# uarthid.net
KiCad netlist of a schematic drawn in EAGLE
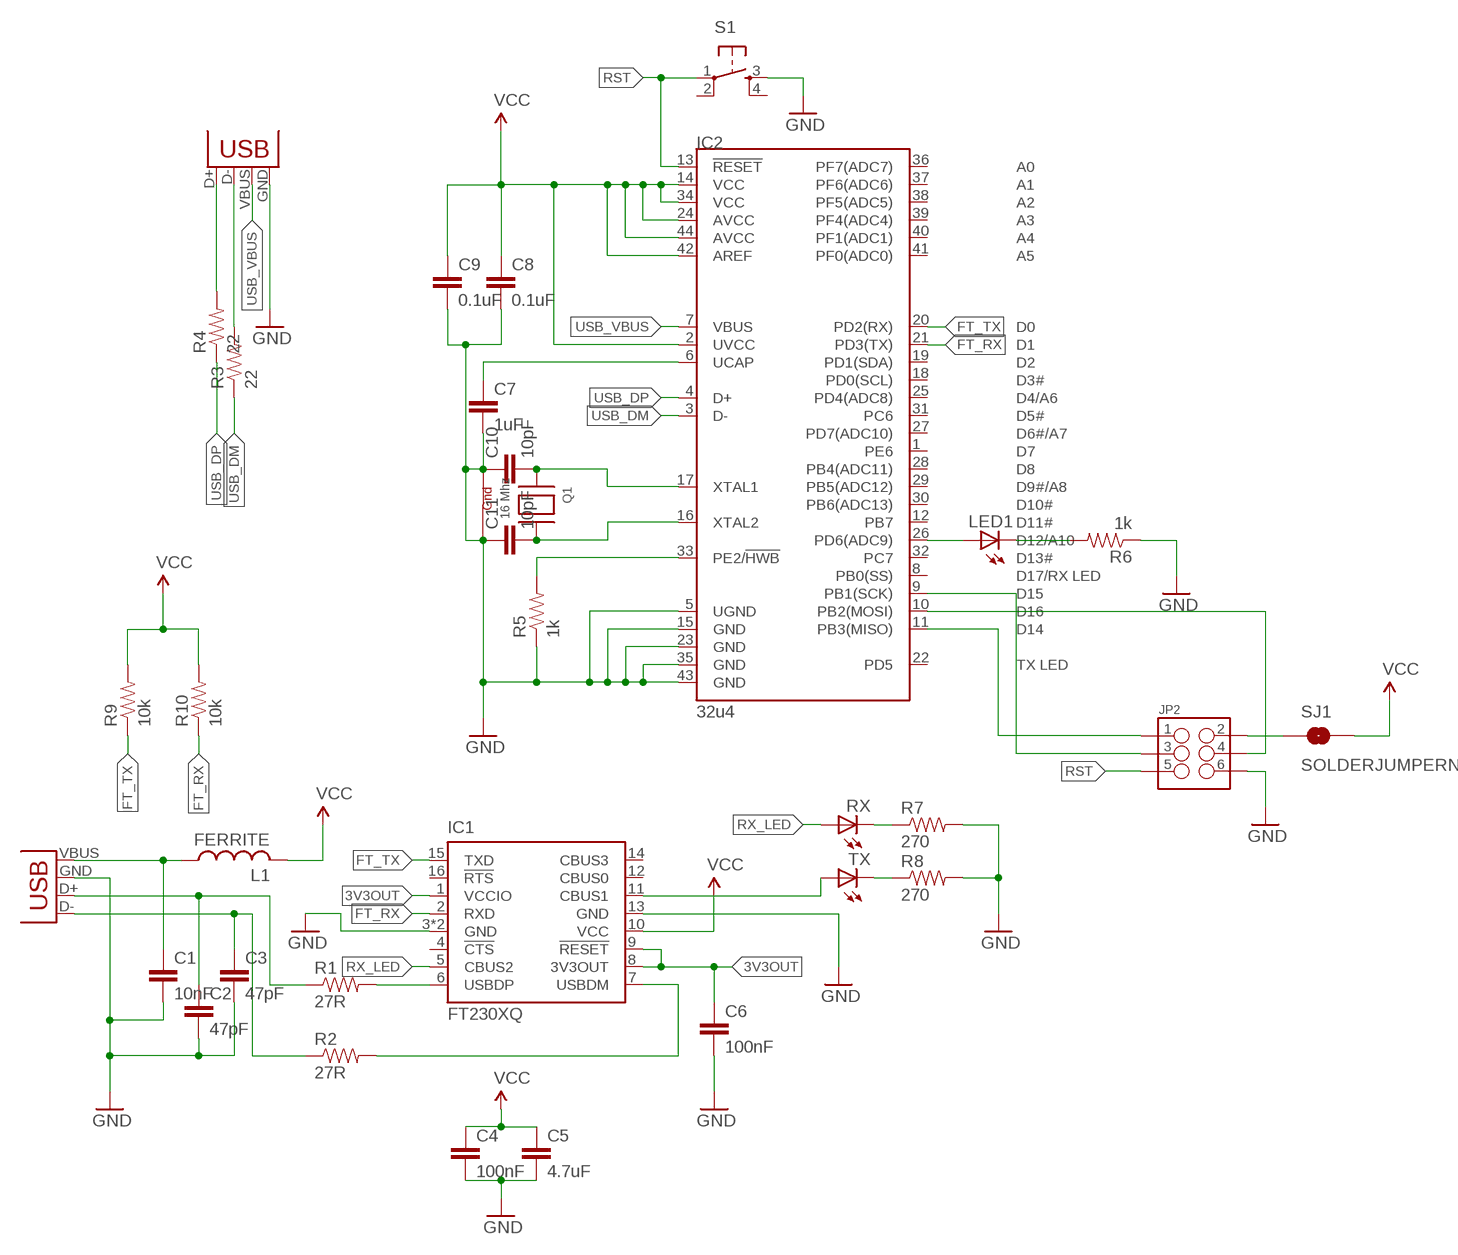
[diagram p0: schematic, sheet 1]

(export (version "E")
  (design (tool "Eeschema 10.0.6"))
  (components
    (comp (ref "C1")
      (value "10nF")
      (footprint "eagle-import:0805")
      (libsource (lib "eagle-import") (part "CAP0805"))
    )
    (comp (ref "C2")
      (value "47pF")
      (footprint "eagle-import:0805")
      (libsource (lib "eagle-import") (part "CAP0805"))
    )
    (comp (ref "C3")
      (value "47pF")
      (footprint "eagle-import:0805")
      (libsource (lib "eagle-import") (part "CAP0805"))
    )
    (comp (ref "C4")
      (value "100nF")
      (footprint "eagle-import:0805")
      (libsource (lib "eagle-import") (part "CAP0805"))
    )
    (comp (ref "C5")
      (value "4.7uF")
      (footprint "eagle-import:0805")
      (libsource (lib "eagle-import") (part "CAP0805"))
    )
    (comp (ref "C6")
      (value "100nF")
      (footprint "eagle-import:0805")
      (libsource (lib "eagle-import") (part "CAP0805"))
    )
    (comp (ref "C7")
      (value "1uF")
      (footprint "eagle-import:0805")
      (libsource (lib "eagle-import") (part "CAP0805"))
    )
    (comp (ref "C8")
      (value "0.1uF")
      (footprint "eagle-import:0805")
      (libsource (lib "eagle-import") (part "CAP0805"))
    )
    (comp (ref "C9")
      (value "0.1uF")
      (footprint "eagle-import:0805")
      (libsource (lib "eagle-import") (part "CAP0805"))
    )
    (comp (ref "C10")
      (value "10pF")
      (footprint "eagle-import:0805")
      (libsource (lib "eagle-import") (part "CAP0805"))
    )
    (comp (ref "C11")
      (value "10pF")
      (footprint "eagle-import:0805")
      (libsource (lib "eagle-import") (part "CAP0805"))
    )
    (comp (ref "IC1")
      (value "FT230XQ")
      (footprint "eagle-import:QFN16")
      (fields (field (name "PARTNO") "FT230XQ-T"))
      (libsource (lib "eagle-import") (part "FT230XQ"))
    )
    (comp (ref "IC2")
      (value "32u4")
      (footprint "eagle-import:SPARKFUN-DIGITALIC_QFN-44")
      (fields (field (name "PARTNO") "ATMEGA32U4RC-MU"))
      (libsource (lib "eagle-import") (part "ATMEGA32U4QFN"))
    )
    (comp (ref "JP1")
      (value "USB-A-H")
      (footprint "eagle-import:USB-A-H")
      (fields (field (name "PARTNO") "1002-015-01001"))
      (libsource (lib "eagle-import") (part "USB-A-H"))
    )
    (comp (ref "JP2")
      (value "M03X22X3_SILK_SM")
      (footprint "eagle-import:2X3")
      (libsource (lib "eagle-import") (part "M03X22X3_SILK_SM"))
    )
    (comp (ref "JP3")
      (value "USBSMD")
      (footprint "eagle-import:USB-MINIB")
      (fields (field (name "PARTNO") "690-005-299-043"))
      (libsource (lib "eagle-import") (part "USBSMD"))
    )
    (comp (ref "L1")
      (value "FERRITE")
      (footprint "eagle-import:0805")
      (fields (field (name "PARTNO") "CIM21J601NE"))
      (libsource (lib "eagle-import") (part "FERRITE"))
    )
    (comp (ref "LED1")
      (value "LEDCHIPLED_0805")
      (footprint "eagle-import:CHIPLED_0805")
      (libsource (lib "eagle-import") (part "LEDCHIPLED_0805"))
    )
    (comp (ref "Q1")
      (value "16 Mhz")
      (footprint "eagle-import:NX3225")
      (fields (field (name "PARTNO") "TSX-3225 16.0000MF18X-AC3"))
      (libsource (lib "eagle-import") (part "XTAL-4-3225"))
    )
    (comp (ref "R1")
      (value "27R")
      (footprint "eagle-import:0805")
      (libsource (lib "eagle-import") (part "RESISTOR0805-RES"))
    )
    (comp (ref "R2")
      (value "27R")
      (footprint "eagle-import:0805")
      (libsource (lib "eagle-import") (part "RESISTOR0805-RES"))
    )
    (comp (ref "R3")
      (value "22")
      (footprint "eagle-import:0805")
      (libsource (lib "eagle-import") (part "RESISTOR0805-RES"))
    )
    (comp (ref "R4")
      (value "22")
      (footprint "eagle-import:0805")
      (libsource (lib "eagle-import") (part "RESISTOR0805-RES"))
    )
    (comp (ref "R5")
      (value "1k")
      (footprint "eagle-import:0805")
      (libsource (lib "eagle-import") (part "RESISTOR0805-RES"))
    )
    (comp (ref "R6")
      (value "1k")
      (footprint "eagle-import:0805")
      (libsource (lib "eagle-import") (part "RESISTOR0805-RES"))
    )
    (comp (ref "R7")
      (value "270")
      (footprint "eagle-import:0805")
      (libsource (lib "eagle-import") (part "RESISTOR0805-RES"))
    )
    (comp (ref "R8")
      (value "270")
      (footprint "eagle-import:0805")
      (libsource (lib "eagle-import") (part "RESISTOR0805-RES"))
    )
    (comp (ref "R9")
      (value "10k")
      (footprint "eagle-import:0805")
      (libsource (lib "eagle-import") (part "RESISTOR0805-RES"))
    )
    (comp (ref "R10")
      (value "10k")
      (footprint "eagle-import:0805")
      (libsource (lib "eagle-import") (part "RESISTOR0805-RES"))
    )
    (comp (ref "RX")
      (value "LEDCHIPLED_0805")
      (footprint "eagle-import:CHIPLED_0805")
      (libsource (lib "eagle-import") (part "LEDCHIPLED_0805"))
    )
    (comp (ref "S1")
      (value "TAC_SWITCHSMD")
      (footprint "eagle-import:TACTILE_SWITCH_SMD")
      (libsource (lib "eagle-import") (part "TAC_SWITCHSMD"))
    )
    (comp (ref "SJ1")
      (value "SOLDERJUMPERNO")
      (footprint "eagle-import:SJ_2S-NO")
      (libsource (lib "eagle-import") (part "SOLDERJUMPERNO"))
    )
    (comp (ref "TX")
      (value "LEDCHIPLED_0805")
      (footprint "eagle-import:CHIPLED_0805")
      (libsource (lib "eagle-import") (part "LEDCHIPLED_0805"))
    )
  )
  (nets
    (net (code "1") (name "3V3OUT") (class "Default")
      (node (ref "C6") (pin "1") (pinfunction "1_1") (pintype "passive"))
      (node (ref "IC1") (pin "1") (pinfunction "VCCIO_1") (pintype "power_in"))
      (node (ref "IC1") (pin "8") (pinfunction "3V3OUT_8") (pintype "output"))
      (node (ref "IC1") (pin "9") (pinfunction "~{RESET}_9") (pintype "input"))
    )
    (net (code "2") (name "FT_RX") (class "Default")
      (node (ref "IC1") (pin "2") (pinfunction "RXD_2") (pintype "input"))
      (node (ref "IC2") (pin "21") (pinfunction "PD3(TX)_21") (pintype "bidirectional"))
      (node (ref "R10") (pin "1") (pinfunction "1_1") (pintype "passive"))
    )
    (net (code "3") (name "FT_TX") (class "Default")
      (node (ref "IC1") (pin "15") (pinfunction "TXD_15") (pintype "output"))
      (node (ref "IC2") (pin "20") (pinfunction "PD2(RX)_20") (pintype "bidirectional"))
      (node (ref "R9") (pin "1") (pinfunction "1_1") (pintype "passive"))
    )
    (net (code "4") (name "GND") (class "Default")
      (node (ref "C1") (pin "2") (pinfunction "2_2") (pintype "passive"))
      (node (ref "C10") (pin "1") (pinfunction "1_1") (pintype "passive"))
      (node (ref "C11") (pin "1") (pinfunction "1_1") (pintype "passive"))
      (node (ref "C2") (pin "2") (pinfunction "2_2") (pintype "passive"))
      (node (ref "C3") (pin "2") (pinfunction "2_2") (pintype "passive"))
      (node (ref "C4") (pin "2") (pinfunction "2_2") (pintype "passive"))
      (node (ref "C5") (pin "2") (pinfunction "2_2") (pintype "passive"))
      (node (ref "C6") (pin "2") (pinfunction "2_2") (pintype "passive"))
      (node (ref "C7") (pin "2") (pinfunction "2_2") (pintype "passive"))
      (node (ref "C8") (pin "2") (pinfunction "2_2") (pintype "passive"))
      (node (ref "C9") (pin "2") (pinfunction "2_2") (pintype "passive"))
      (node (ref "IC1") (pin "13") (pinfunction "GND_13") (pintype "power_in"))
      (node (ref "IC1") (pin "3") (pinfunction "GND_3") (pintype "power_in"))
      (node (ref "IC1") (pin "TAB") (pinfunction "GND_TAB") (pintype "power_in"))
      (node (ref "IC2") (pin "15") (pinfunction "GND_15") (pintype "bidirectional"))
      (node (ref "IC2") (pin "23") (pinfunction "GND_23") (pintype "bidirectional"))
      (node (ref "IC2") (pin "35") (pinfunction "GND_35") (pintype "bidirectional"))
      (node (ref "IC2") (pin "43") (pinfunction "GND_43") (pintype "bidirectional"))
      (node (ref "IC2") (pin "5") (pinfunction "UGND_5") (pintype "bidirectional"))
      (node (ref "JP1") (pin "GND") (pinfunction "VBUS_GND") (pintype "bidirectional"))
      (node (ref "JP2") (pin "6") (pinfunction "6_6") (pintype "bidirectional"))
      (node (ref "JP3") (pin "GND") (pinfunction "GND_GND") (pintype "bidirectional"))
      (node (ref "Q1") (pin "2") (pinfunction "G2_2") (pintype "power_in"))
      (node (ref "Q1") (pin "4") (pinfunction "G1_4") (pintype "power_in"))
      (node (ref "R5") (pin "1") (pinfunction "1_1") (pintype "passive"))
      (node (ref "R6") (pin "1") (pinfunction "1_1") (pintype "passive"))
      (node (ref "R7") (pin "2") (pinfunction "2_2") (pintype "passive"))
      (node (ref "R8") (pin "2") (pinfunction "2_2") (pintype "passive"))
      (node (ref "S1") (pin "3") (pinfunction "3_3") (pintype "passive"))
    )
    (net (code "5") (name "Net-(IC1-CBUS1)") (class "Default")
      (node (ref "IC1") (pin "11") (pinfunction "CBUS1_11") (pintype "bidirectional"))
      (node (ref "TX") (pin "A") (pinfunction "A_A") (pintype "passive"))
    )
    (net (code "6") (name "Net-(IC1-USBDM)") (class "Default")
      (node (ref "IC1") (pin "7") (pinfunction "USBDM_7") (pintype "input"))
      (node (ref "R2") (pin "2") (pinfunction "2_2") (pintype "passive"))
    )
    (net (code "7") (name "Net-(IC1-USBDP)") (class "Default")
      (node (ref "IC1") (pin "6") (pinfunction "USBDP_6") (pintype "input"))
      (node (ref "R1") (pin "2") (pinfunction "2_2") (pintype "passive"))
    )
    (net (code "8") (name "Net-(IC2-PB1(SCK))") (class "Default")
      (node (ref "IC2") (pin "9") (pinfunction "PB1(SCK)_9") (pintype "bidirectional"))
      (node (ref "JP2") (pin "3") (pinfunction "3_3") (pintype "bidirectional"))
    )
    (net (code "9") (name "Net-(IC2-PB2(MOSI))") (class "Default")
      (node (ref "IC2") (pin "10") (pinfunction "PB2(MOSI)_10") (pintype "bidirectional"))
      (node (ref "JP2") (pin "4") (pinfunction "4_4") (pintype "bidirectional"))
    )
    (net (code "10") (name "Net-(IC2-PB3(MISO))") (class "Default")
      (node (ref "IC2") (pin "11") (pinfunction "PB3(MISO)_11") (pintype "bidirectional"))
      (node (ref "JP2") (pin "1") (pinfunction "1_1") (pintype "bidirectional"))
    )
    (net (code "11") (name "Net-(IC2-PD6(ADC9))") (class "Default")
      (node (ref "IC2") (pin "26") (pinfunction "PD6(ADC9)_26") (pintype "bidirectional"))
      (node (ref "LED1") (pin "A") (pinfunction "A_A") (pintype "passive"))
    )
    (net (code "12") (name "Net-(IC2-PE2{slash}~{HWB})") (class "Default")
      (node (ref "IC2") (pin "33") (pinfunction "PE2/~{HWB}_33") (pintype "bidirectional"))
      (node (ref "R5") (pin "2") (pinfunction "2_2") (pintype "passive"))
    )
    (net (code "13") (name "Net-(IC2-UCAP)") (class "Default")
      (node (ref "C7") (pin "1") (pinfunction "1_1") (pintype "passive"))
      (node (ref "IC2") (pin "6") (pinfunction "UCAP_6") (pintype "bidirectional"))
    )
    (net (code "14") (name "Net-(IC2-XTAL1)") (class "Default")
      (node (ref "C10") (pin "2") (pinfunction "2_2") (pintype "passive"))
      (node (ref "IC2") (pin "17") (pinfunction "XTAL1_17") (pintype "bidirectional"))
      (node (ref "Q1") (pin "1") (pinfunction "X1_1") (pintype "bidirectional"))
    )
    (net (code "15") (name "Net-(IC2-XTAL2)") (class "Default")
      (node (ref "C11") (pin "2") (pinfunction "2_2") (pintype "passive"))
      (node (ref "IC2") (pin "16") (pinfunction "XTAL2_16") (pintype "bidirectional"))
      (node (ref "Q1") (pin "3") (pinfunction "X2_3") (pintype "bidirectional"))
    )
    (net (code "16") (name "Net-(JP1-D+)") (class "Default")
      (node (ref "C3") (pin "1") (pinfunction "1_1") (pintype "passive"))
      (node (ref "JP1") (pin "D-") (pinfunction "D+_D-") (pintype "bidirectional"))
      (node (ref "R2") (pin "1") (pinfunction "1_1") (pintype "passive"))
    )
    (net (code "17") (name "Net-(JP1-D-)") (class "Default")
      (node (ref "C2") (pin "1") (pinfunction "1_1") (pintype "passive"))
      (node (ref "JP1") (pin "D+") (pinfunction "D-_D+") (pintype "bidirectional"))
      (node (ref "R1") (pin "1") (pinfunction "1_1") (pintype "passive"))
    )
    (net (code "18") (name "Net-(JP1-GND)") (class "Default")
      (node (ref "C1") (pin "1") (pinfunction "1_1") (pintype "passive"))
      (node (ref "JP1") (pin "VBUS") (pinfunction "GND_VBUS") (pintype "bidirectional"))
      (node (ref "L1") (pin "1") (pinfunction "1_1") (pintype "passive"))
    )
    (net (code "19") (name "Net-(JP2-Pad2)") (class "Default")
      (node (ref "JP2") (pin "2") (pinfunction "2_2") (pintype "bidirectional"))
      (node (ref "SJ1") (pin "1") (pinfunction "1_1") (pintype "passive"))
    )
    (net (code "20") (name "Net-(JP3-PadD+)") (class "Default")
      (node (ref "JP3") (pin "D+") (pinfunction "D+_D+") (pintype "bidirectional"))
      (node (ref "R4") (pin "2") (pinfunction "2_2") (pintype "passive"))
    )
    (net (code "21") (name "Net-(JP3-PadD-)") (class "Default")
      (node (ref "JP3") (pin "D-") (pinfunction "D-_D-") (pintype "bidirectional"))
      (node (ref "R3") (pin "2") (pinfunction "2_2") (pintype "passive"))
    )
    (net (code "22") (name "Net-(LED1-PadC)") (class "Default")
      (node (ref "LED1") (pin "C") (pinfunction "C_C") (pintype "passive"))
      (node (ref "R6") (pin "2") (pinfunction "2_2") (pintype "passive"))
    )
    (net (code "23") (name "Net-(R7-Pad1)") (class "Default")
      (node (ref "R7") (pin "1") (pinfunction "1_1") (pintype "passive"))
      (node (ref "RX") (pin "C") (pinfunction "C_C") (pintype "passive"))
    )
    (net (code "24") (name "Net-(R8-Pad1)") (class "Default")
      (node (ref "R8") (pin "1") (pinfunction "1_1") (pintype "passive"))
      (node (ref "TX") (pin "C") (pinfunction "C_C") (pintype "passive"))
    )
    (net (code "25") (name "RST") (class "Default")
      (node (ref "IC2") (pin "13") (pinfunction "~{RESET}_13") (pintype "bidirectional"))
      (node (ref "JP2") (pin "5") (pinfunction "5_5") (pintype "bidirectional"))
      (node (ref "S1") (pin "1") (pinfunction "1_1") (pintype "passive"))
    )
    (net (code "26") (name "RX_LED") (class "Default")
      (node (ref "IC1") (pin "5") (pinfunction "CBUS2_5") (pintype "bidirectional"))
      (node (ref "RX") (pin "A") (pinfunction "A_A") (pintype "passive"))
    )
    (net (code "27") (name "USB_DM") (class "Default")
      (node (ref "IC2") (pin "3") (pinfunction "D-_3") (pintype "bidirectional"))
      (node (ref "R3") (pin "1") (pinfunction "1_1") (pintype "passive"))
    )
    (net (code "28") (name "USB_DP") (class "Default")
      (node (ref "IC2") (pin "4") (pinfunction "D+_4") (pintype "bidirectional"))
      (node (ref "R4") (pin "1") (pinfunction "1_1") (pintype "passive"))
    )
    (net (code "29") (name "USB_VBUS") (class "Default")
      (node (ref "IC2") (pin "7") (pinfunction "VBUS_7") (pintype "bidirectional"))
      (node (ref "JP3") (pin "VBUS") (pinfunction "VBUS_VBUS") (pintype "bidirectional"))
    )
    (net (code "30") (name "VCC") (class "Default")
      (node (ref "C4") (pin "1") (pinfunction "1_1") (pintype "passive"))
      (node (ref "C5") (pin "1") (pinfunction "1_1") (pintype "passive"))
      (node (ref "C8") (pin "1") (pinfunction "1_1") (pintype "passive"))
      (node (ref "C9") (pin "1") (pinfunction "1_1") (pintype "passive"))
      (node (ref "IC1") (pin "10") (pinfunction "VCC_10") (pintype "power_in"))
      (node (ref "IC2") (pin "14") (pinfunction "VCC_14") (pintype "bidirectional"))
      (node (ref "IC2") (pin "2") (pinfunction "UVCC_2") (pintype "bidirectional"))
      (node (ref "IC2") (pin "24") (pinfunction "AVCC_24") (pintype "bidirectional"))
      (node (ref "IC2") (pin "34") (pinfunction "VCC_34") (pintype "bidirectional"))
      (node (ref "IC2") (pin "42") (pinfunction "AREF_42") (pintype "bidirectional"))
      (node (ref "IC2") (pin "44") (pinfunction "AVCC_44") (pintype "bidirectional"))
      (node (ref "L1") (pin "2") (pinfunction "2_2") (pintype "passive"))
      (node (ref "R10") (pin "2") (pinfunction "2_2") (pintype "passive"))
      (node (ref "R9") (pin "2") (pinfunction "2_2") (pintype "passive"))
      (node (ref "SJ1") (pin "2") (pinfunction "2_2") (pintype "passive"))
    )
    (net (code "31") (name "unconnected-(IC1-CBUS0-Pad12)") (class "Default")
      (node (ref "IC1") (pin "12") (pinfunction "CBUS0_12") (pintype "bidirectional"))
    )
    (net (code "32") (name "unconnected-(IC1-CBUS3-Pad14)") (class "Default")
      (node (ref "IC1") (pin "14") (pinfunction "CBUS3_14") (pintype "bidirectional"))
    )
    (net (code "33") (name "unconnected-(IC1-~{CTS}-Pad4)") (class "Default")
      (node (ref "IC1") (pin "4") (pinfunction "~{CTS}_4") (pintype "input"))
    )
    (net (code "34") (name "unconnected-(IC1-~{RTS}-Pad16)") (class "Default")
      (node (ref "IC1") (pin "16") (pinfunction "~{RTS}_16") (pintype "output"))
    )
    (net (code "35") (name "unconnected-(IC2-PB0(SS)-Pad8)") (class "Default")
      (node (ref "IC2") (pin "8") (pinfunction "PB0(SS)_8") (pintype "bidirectional"))
    )
    (net (code "36") (name "unconnected-(IC2-PB4(ADC11)-Pad28)") (class "Default")
      (node (ref "IC2") (pin "28") (pinfunction "PB4(ADC11)_28") (pintype "bidirectional"))
    )
    (net (code "37") (name "unconnected-(IC2-PB5(ADC12)-Pad29)") (class "Default")
      (node (ref "IC2") (pin "29") (pinfunction "PB5(ADC12)_29") (pintype "bidirectional"))
    )
    (net (code "38") (name "unconnected-(IC2-PB6(ADC13)-Pad30)") (class "Default")
      (node (ref "IC2") (pin "30") (pinfunction "PB6(ADC13)_30") (pintype "bidirectional"))
    )
    (net (code "39") (name "unconnected-(IC2-PB7-Pad12)") (class "Default")
      (node (ref "IC2") (pin "12") (pinfunction "PB7_12") (pintype "bidirectional"))
    )
    (net (code "40") (name "unconnected-(IC2-PC6-Pad31)") (class "Default")
      (node (ref "IC2") (pin "31") (pinfunction "PC6_31") (pintype "bidirectional"))
    )
    (net (code "41") (name "unconnected-(IC2-PC7-Pad32)") (class "Default")
      (node (ref "IC2") (pin "32") (pinfunction "PC7_32") (pintype "bidirectional"))
    )
    (net (code "42") (name "unconnected-(IC2-PD0(SCL)-Pad18)") (class "Default")
      (node (ref "IC2") (pin "18") (pinfunction "PD0(SCL)_18") (pintype "bidirectional"))
    )
    (net (code "43") (name "unconnected-(IC2-PD1(SDA)-Pad19)") (class "Default")
      (node (ref "IC2") (pin "19") (pinfunction "PD1(SDA)_19") (pintype "bidirectional"))
    )
    (net (code "44") (name "unconnected-(IC2-PD4(ADC8)-Pad25)") (class "Default")
      (node (ref "IC2") (pin "25") (pinfunction "PD4(ADC8)_25") (pintype "bidirectional"))
    )
    (net (code "45") (name "unconnected-(IC2-PD5-Pad22)") (class "Default")
      (node (ref "IC2") (pin "22") (pinfunction "PD5_22") (pintype "bidirectional"))
    )
    (net (code "46") (name "unconnected-(IC2-PD7(ADC10)-Pad27)") (class "Default")
      (node (ref "IC2") (pin "27") (pinfunction "PD7(ADC10)_27") (pintype "bidirectional"))
    )
    (net (code "47") (name "unconnected-(IC2-PE6-Pad1)") (class "Default")
      (node (ref "IC2") (pin "1") (pinfunction "PE6_1") (pintype "bidirectional"))
    )
    (net (code "48") (name "unconnected-(IC2-PF0(ADC0)-Pad41)") (class "Default")
      (node (ref "IC2") (pin "41") (pinfunction "PF0(ADC0)_41") (pintype "bidirectional"))
    )
    (net (code "49") (name "unconnected-(IC2-PF1(ADC1)-Pad40)") (class "Default")
      (node (ref "IC2") (pin "40") (pinfunction "PF1(ADC1)_40") (pintype "bidirectional"))
    )
    (net (code "50") (name "unconnected-(IC2-PF4(ADC4)-Pad39)") (class "Default")
      (node (ref "IC2") (pin "39") (pinfunction "PF4(ADC4)_39") (pintype "bidirectional"))
    )
    (net (code "51") (name "unconnected-(IC2-PF5(ADC5)-Pad38)") (class "Default")
      (node (ref "IC2") (pin "38") (pinfunction "PF5(ADC5)_38") (pintype "bidirectional"))
    )
    (net (code "52") (name "unconnected-(IC2-PF6(ADC6)-Pad37)") (class "Default")
      (node (ref "IC2") (pin "37") (pinfunction "PF6(ADC6)_37") (pintype "bidirectional"))
    )
    (net (code "53") (name "unconnected-(IC2-PF7(ADC7)-Pad36)") (class "Default")
      (node (ref "IC2") (pin "36") (pinfunction "PF7(ADC7)_36") (pintype "bidirectional"))
    )
    (net (code "54") (name "unconnected-(S1-Pad2)") (class "Default")
      (node (ref "S1") (pin "2") (pinfunction "2_2") (pintype "passive"))
    )
    (net (code "55") (name "unconnected-(S1-Pad4)") (class "Default")
      (node (ref "S1") (pin "4") (pinfunction "4_4") (pintype "passive"))
    )
  )
)
